# MotorController.net
KiCad netlist of a schematic drawn in Altium Designer
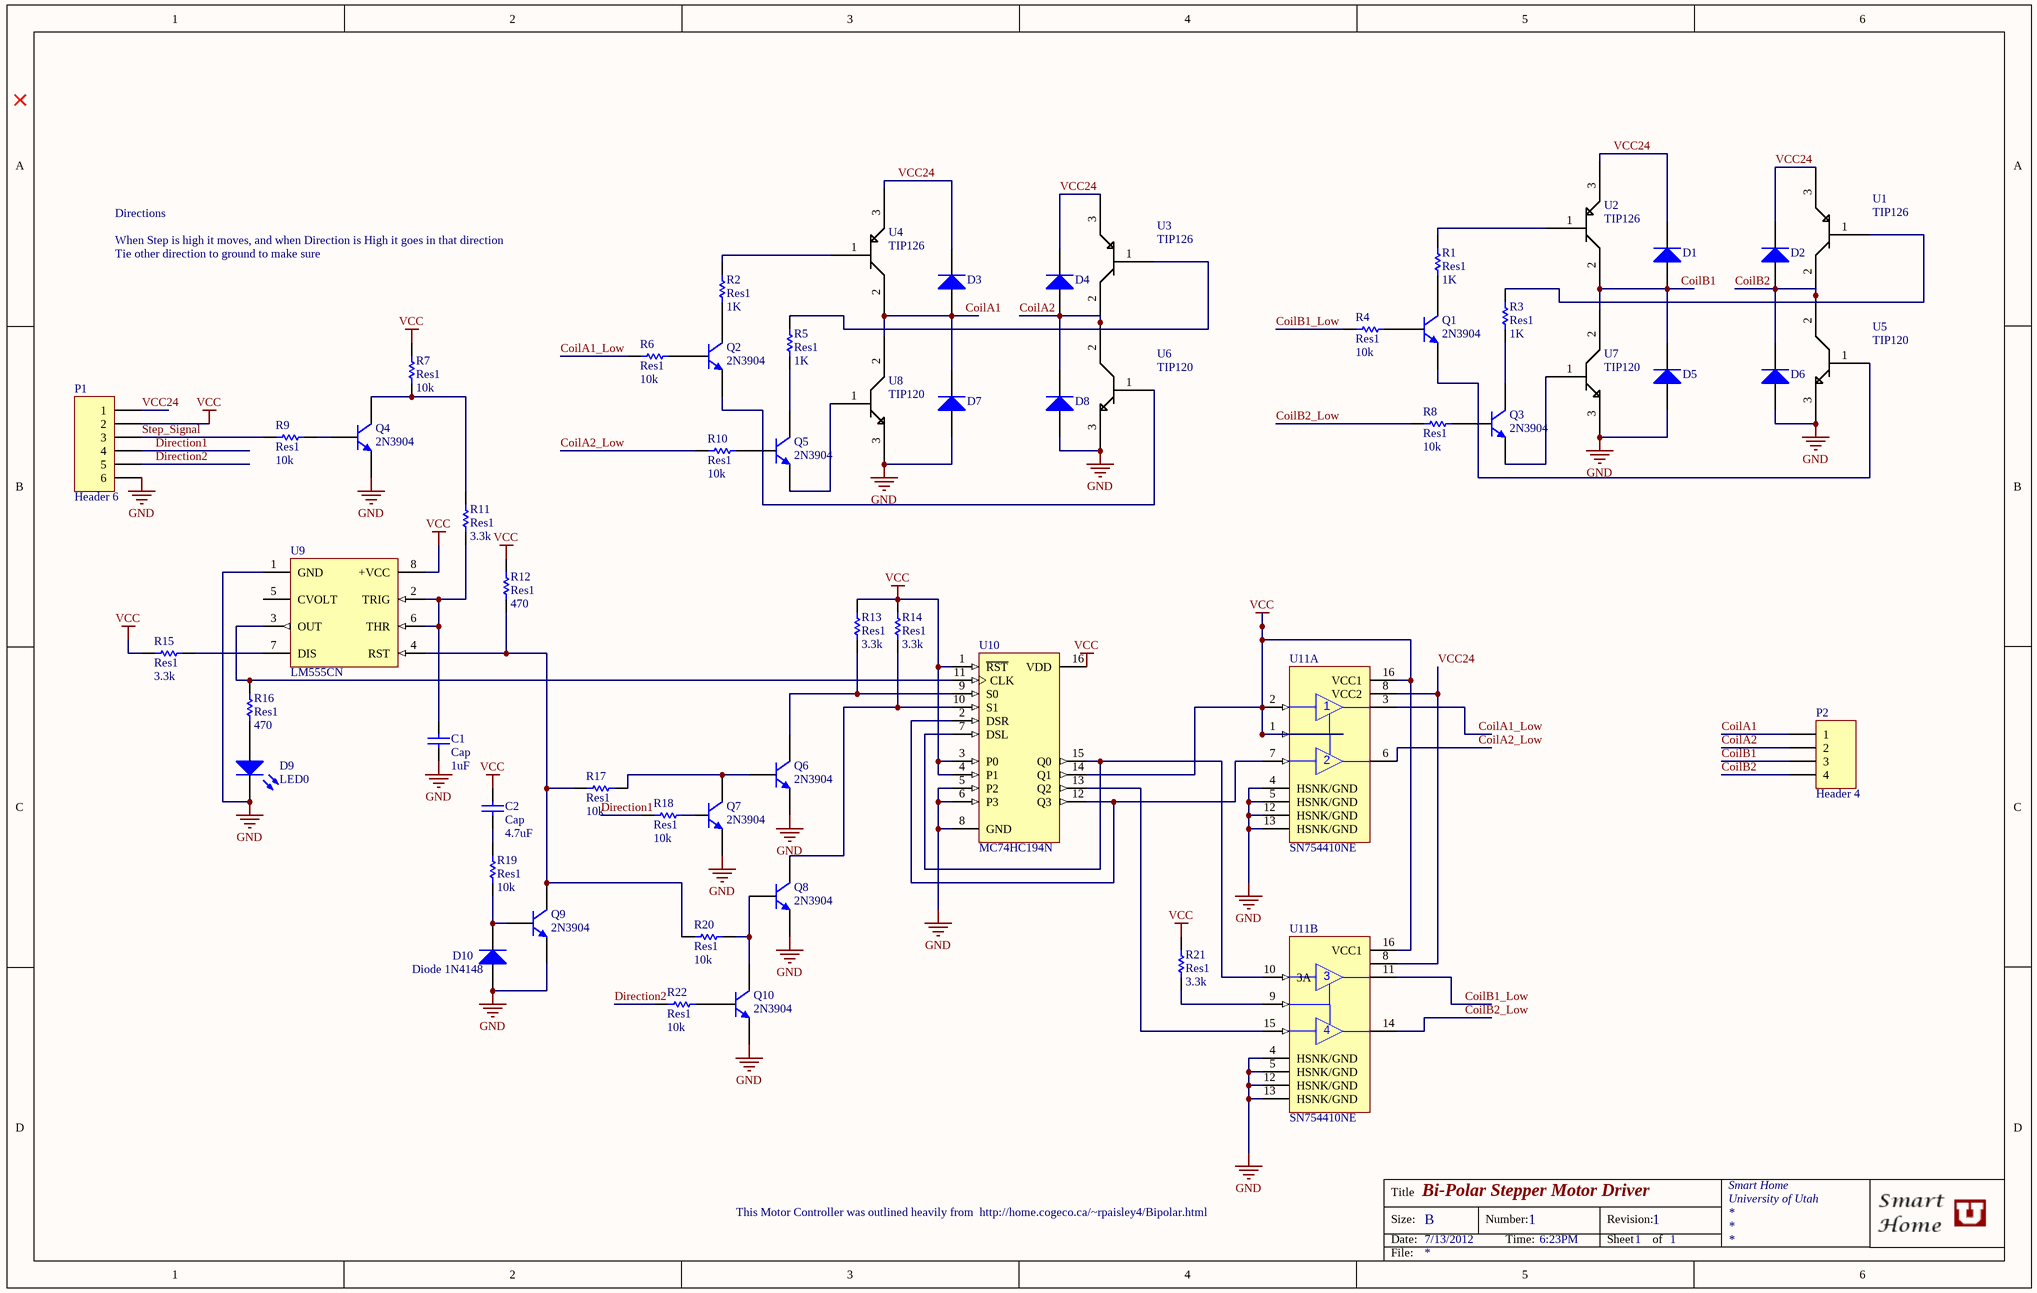
[diagram p0: MotorController.SchDoc]

(export (version "E")
  (design (tool "Eeschema 10.0.6"))
  (components
    (comp (ref "C1")
      (value "Cap")
      (footprint "RAD-0.3")
      (description "Capacitor")
      (fields (field (name "ALTIUM_VALUE") "1uF") (field (name "PUBLISHER") "Altium Limited"))
      (libsource (lib "Miscellaneous Devices") (part "Cap"))
    )
    (comp (ref "C2")
      (value "Cap")
      (footprint "RAD-0.3")
      (description "Capacitor")
      (fields (field (name "ALTIUM_VALUE") "4.7uF") (field (name "PUBLISHER") "Altium Limited"))
      (libsource (lib "Miscellaneous Devices") (part "Cap"))
    )
    (comp (ref "D1")
      (value "Diode 1N5408")
      (footprint "DO-201AD")
      (description "3 Amp Medium Power Silicon Rectifier Diode")
      (fields (field (name "PUBLISHER") "Altium Limited"))
      (libsource (lib "Miscellaneous Devices") (part "Diode 1N5408"))
    )
    (comp (ref "D2")
      (value "Diode 1N5408")
      (footprint "DO-201AD")
      (description "3 Amp Medium Power Silicon Rectifier Diode")
      (fields (field (name "PUBLISHER") "Altium Limited"))
      (libsource (lib "Miscellaneous Devices") (part "Diode 1N5408"))
    )
    (comp (ref "D3")
      (value "Diode 1N5408")
      (footprint "DO-201AD")
      (description "3 Amp Medium Power Silicon Rectifier Diode")
      (fields (field (name "PUBLISHER") "Altium Limited"))
      (libsource (lib "Miscellaneous Devices") (part "Diode 1N5408"))
    )
    (comp (ref "D4")
      (value "Diode 1N5408")
      (footprint "DO-201AD")
      (description "3 Amp Medium Power Silicon Rectifier Diode")
      (fields (field (name "PUBLISHER") "Altium Limited"))
      (libsource (lib "Miscellaneous Devices") (part "Diode 1N5408"))
    )
    (comp (ref "D5")
      (value "Diode 1N5408")
      (footprint "DO-201AD")
      (description "3 Amp Medium Power Silicon Rectifier Diode")
      (fields (field (name "PUBLISHER") "Altium Limited"))
      (libsource (lib "Miscellaneous Devices") (part "Diode 1N5408"))
    )
    (comp (ref "D6")
      (value "Diode 1N5408")
      (footprint "DO-201AD")
      (description "3 Amp Medium Power Silicon Rectifier Diode")
      (fields (field (name "PUBLISHER") "Altium Limited"))
      (libsource (lib "Miscellaneous Devices") (part "Diode 1N5408"))
    )
    (comp (ref "D7")
      (value "Diode 1N5408")
      (footprint "DO-201AD")
      (description "3 Amp Medium Power Silicon Rectifier Diode")
      (fields (field (name "PUBLISHER") "Altium Limited"))
      (libsource (lib "Miscellaneous Devices") (part "Diode 1N5408"))
    )
    (comp (ref "D8")
      (value "Diode 1N5408")
      (footprint "DO-201AD")
      (description "3 Amp Medium Power Silicon Rectifier Diode")
      (fields (field (name "PUBLISHER") "Altium Limited"))
      (libsource (lib "Miscellaneous Devices") (part "Diode 1N5408"))
    )
    (comp (ref "D9")
      (value "LED0")
      (footprint "LED-0")
      (description "Typical INFRARED GaAs LED")
      (fields (field (name "PUBLISHER") "Altium Limited"))
      (libsource (lib "Miscellaneous Devices") (part "LED0"))
    )
    (comp (ref "D10")
      (value "Diode 1N4148")
      (footprint "DO-35")
      (description "High Conductance Fast Diode")
      (fields (field (name "PUBLISHER") "Altium Limited"))
      (libsource (lib "Miscellaneous Devices") (part "Diode 1N4148"))
    )
    (comp (ref "P1")
      (value "Header 6")
      (footprint "HDR1X6")
      (description "Header, 6-Pin")
      (fields (field (name "PUBLISHER") "Altium Limited"))
      (libsource (lib "Miscellaneous Connectors") (part "Header 6"))
    )
    (comp (ref "P2")
      (value "Header 4")
      (footprint "HDR1X4")
      (description "Header, 4-Pin")
      (fields (field (name "PUBLISHER") "Altium Limited"))
      (libsource (lib "Miscellaneous Connectors") (part "Header 4"))
    )
    (comp (ref "Q1")
      (value "2N3904")
      (footprint "2N3904")
      (description "NPN General Purpose Amplifier")
      (fields (field (name "PUBLISHER") "Altium Limited"))
      (libsource (lib "Miscellaneous Devices") (part "2N3904"))
    )
    (comp (ref "Q2")
      (value "2N3904")
      (footprint "2N3904")
      (description "NPN General Purpose Amplifier")
      (fields (field (name "PUBLISHER") "Altium Limited"))
      (libsource (lib "Miscellaneous Devices") (part "2N3904"))
    )
    (comp (ref "Q3")
      (value "2N3904")
      (footprint "2N3904")
      (description "NPN General Purpose Amplifier")
      (fields (field (name "PUBLISHER") "Altium Limited"))
      (libsource (lib "Miscellaneous Devices") (part "2N3904"))
    )
    (comp (ref "Q4")
      (value "2N3904")
      (footprint "2N3904")
      (description "NPN General Purpose Amplifier")
      (fields (field (name "PUBLISHER") "Altium Limited"))
      (libsource (lib "Miscellaneous Devices") (part "2N3904"))
    )
    (comp (ref "Q5")
      (value "2N3904")
      (footprint "2N3904")
      (description "NPN General Purpose Amplifier")
      (fields (field (name "PUBLISHER") "Altium Limited"))
      (libsource (lib "Miscellaneous Devices") (part "2N3904"))
    )
    (comp (ref "Q6")
      (value "2N3904")
      (footprint "2N3904")
      (description "NPN General Purpose Amplifier")
      (fields (field (name "PUBLISHER") "Altium Limited"))
      (libsource (lib "Miscellaneous Devices") (part "2N3904"))
    )
    (comp (ref "Q7")
      (value "2N3904")
      (footprint "2N3904")
      (description "NPN General Purpose Amplifier")
      (fields (field (name "PUBLISHER") "Altium Limited"))
      (libsource (lib "Miscellaneous Devices") (part "2N3904"))
    )
    (comp (ref "Q8")
      (value "2N3904")
      (footprint "2N3904")
      (description "NPN General Purpose Amplifier")
      (fields (field (name "PUBLISHER") "Altium Limited"))
      (libsource (lib "Miscellaneous Devices") (part "2N3904"))
    )
    (comp (ref "Q9")
      (value "2N3904")
      (footprint "2N3904")
      (description "NPN General Purpose Amplifier")
      (fields (field (name "PUBLISHER") "Altium Limited"))
      (libsource (lib "Miscellaneous Devices") (part "2N3904"))
    )
    (comp (ref "Q10")
      (value "2N3904")
      (footprint "2N3904")
      (description "NPN General Purpose Amplifier")
      (fields (field (name "PUBLISHER") "Altium Limited"))
      (libsource (lib "Miscellaneous Devices") (part "2N3904"))
    )
    (comp (ref "R1")
      (value "Res1")
      (footprint "AXIAL-0.3")
      (description "Resistor")
      (fields (field (name "ALTIUM_VALUE") "1K") (field (name "PUBLISHER") "Altium Limited"))
      (libsource (lib "Miscellaneous Devices") (part "Res1"))
    )
    (comp (ref "R2")
      (value "Res1")
      (footprint "AXIAL-0.3")
      (description "Resistor")
      (fields (field (name "ALTIUM_VALUE") "1K") (field (name "PUBLISHER") "Altium Limited"))
      (libsource (lib "Miscellaneous Devices") (part "Res1"))
    )
    (comp (ref "R3")
      (value "Res1")
      (footprint "AXIAL-0.3")
      (description "Resistor")
      (fields (field (name "ALTIUM_VALUE") "1K") (field (name "PUBLISHER") "Altium Limited"))
      (libsource (lib "Miscellaneous Devices") (part "Res1"))
    )
    (comp (ref "R4")
      (value "Res1")
      (footprint "AXIAL-0.3")
      (description "Resistor")
      (fields (field (name "ALTIUM_VALUE") "10k") (field (name "PUBLISHER") "Altium Limited"))
      (libsource (lib "Miscellaneous Devices") (part "Res1"))
    )
    (comp (ref "R5")
      (value "Res1")
      (footprint "AXIAL-0.3")
      (description "Resistor")
      (fields (field (name "ALTIUM_VALUE") "1K") (field (name "PUBLISHER") "Altium Limited"))
      (libsource (lib "Miscellaneous Devices") (part "Res1"))
    )
    (comp (ref "R6")
      (value "Res1")
      (footprint "AXIAL-0.3")
      (description "Resistor")
      (fields (field (name "ALTIUM_VALUE") "10k") (field (name "PUBLISHER") "Altium Limited"))
      (libsource (lib "Miscellaneous Devices") (part "Res1"))
    )
    (comp (ref "R7")
      (value "Res1")
      (footprint "AXIAL-0.3")
      (description "Resistor")
      (fields (field (name "ALTIUM_VALUE") "10k") (field (name "PUBLISHER") "Altium Limited"))
      (libsource (lib "Miscellaneous Devices") (part "Res1"))
    )
    (comp (ref "R8")
      (value "Res1")
      (footprint "AXIAL-0.3")
      (description "Resistor")
      (fields (field (name "ALTIUM_VALUE") "10k") (field (name "PUBLISHER") "Altium Limited"))
      (libsource (lib "Miscellaneous Devices") (part "Res1"))
    )
    (comp (ref "R9")
      (value "Res1")
      (footprint "AXIAL-0.3")
      (description "Resistor")
      (fields (field (name "ALTIUM_VALUE") "10k") (field (name "PUBLISHER") "Altium Limited"))
      (libsource (lib "Miscellaneous Devices") (part "Res1"))
    )
    (comp (ref "R10")
      (value "Res1")
      (footprint "AXIAL-0.3")
      (description "Resistor")
      (fields (field (name "ALTIUM_VALUE") "10k") (field (name "PUBLISHER") "Altium Limited"))
      (libsource (lib "Miscellaneous Devices") (part "Res1"))
    )
    (comp (ref "R11")
      (value "Res1")
      (footprint "AXIAL-0.3")
      (description "Resistor")
      (fields (field (name "ALTIUM_VALUE") "3.3k") (field (name "PUBLISHER") "Altium Limited"))
      (libsource (lib "Miscellaneous Devices") (part "Res1"))
    )
    (comp (ref "R12")
      (value "Res1")
      (footprint "AXIAL-0.3")
      (description "Resistor")
      (fields (field (name "ALTIUM_VALUE") "470") (field (name "PUBLISHER") "Altium Limited"))
      (libsource (lib "Miscellaneous Devices") (part "Res1"))
    )
    (comp (ref "R13")
      (value "Res1")
      (footprint "AXIAL-0.3")
      (description "Resistor")
      (fields (field (name "ALTIUM_VALUE") "3.3k") (field (name "PUBLISHER") "Altium Limited"))
      (libsource (lib "Miscellaneous Devices") (part "Res1"))
    )
    (comp (ref "R14")
      (value "Res1")
      (footprint "AXIAL-0.3")
      (description "Resistor")
      (fields (field (name "ALTIUM_VALUE") "3.3k") (field (name "PUBLISHER") "Altium Limited"))
      (libsource (lib "Miscellaneous Devices") (part "Res1"))
    )
    (comp (ref "R15")
      (value "Res1")
      (footprint "AXIAL-0.3")
      (description "Resistor")
      (fields (field (name "ALTIUM_VALUE") "3.3k") (field (name "PUBLISHER") "Altium Limited"))
      (libsource (lib "Miscellaneous Devices") (part "Res1"))
    )
    (comp (ref "R16")
      (value "Res1")
      (footprint "AXIAL-0.3")
      (description "Resistor")
      (fields (field (name "ALTIUM_VALUE") "470") (field (name "PUBLISHER") "Altium Limited"))
      (libsource (lib "Miscellaneous Devices") (part "Res1"))
    )
    (comp (ref "R17")
      (value "Res1")
      (footprint "AXIAL-0.3")
      (description "Resistor")
      (fields (field (name "ALTIUM_VALUE") "10k") (field (name "PUBLISHER") "Altium Limited"))
      (libsource (lib "Miscellaneous Devices") (part "Res1"))
    )
    (comp (ref "R18")
      (value "Res1")
      (footprint "AXIAL-0.3")
      (description "Resistor")
      (fields (field (name "ALTIUM_VALUE") "10k") (field (name "PUBLISHER") "Altium Limited"))
      (libsource (lib "Miscellaneous Devices") (part "Res1"))
    )
    (comp (ref "R19")
      (value "Res1")
      (footprint "AXIAL-0.3")
      (description "Resistor")
      (fields (field (name "ALTIUM_VALUE") "10k") (field (name "PUBLISHER") "Altium Limited"))
      (libsource (lib "Miscellaneous Devices") (part "Res1"))
    )
    (comp (ref "R20")
      (value "Res1")
      (footprint "AXIAL-0.3")
      (description "Resistor")
      (fields (field (name "ALTIUM_VALUE") "10k") (field (name "PUBLISHER") "Altium Limited"))
      (libsource (lib "Miscellaneous Devices") (part "Res1"))
    )
    (comp (ref "R21")
      (value "Res1")
      (footprint "AXIAL-0.3")
      (description "Resistor")
      (fields (field (name "ALTIUM_VALUE") "3.3k") (field (name "PUBLISHER") "Altium Limited"))
      (libsource (lib "Miscellaneous Devices") (part "Res1"))
    )
    (comp (ref "R22")
      (value "Res1")
      (footprint "AXIAL-0.3")
      (description "Resistor")
      (fields (field (name "ALTIUM_VALUE") "10k") (field (name "PUBLISHER") "Altium Limited"))
      (libsource (lib "Miscellaneous Devices") (part "Res1"))
    )
    (comp (ref "U1")
      (value "TIP126")
      (footprint "TO-220")
      (description "TIP126 -PNP")
      (libsource (lib "SeniorProjectLibrary") (part "TIP126"))
    )
    (comp (ref "U2")
      (value "TIP126")
      (footprint "TO-220")
      (description "TIP126 -PNP")
      (libsource (lib "SeniorProjectLibrary") (part "TIP126"))
    )
    (comp (ref "U3")
      (value "TIP126")
      (footprint "TO-220")
      (description "TIP126 -PNP")
      (libsource (lib "SeniorProjectLibrary") (part "TIP126"))
    )
    (comp (ref "U4")
      (value "TIP126")
      (footprint "TO-220")
      (description "TIP126 -PNP")
      (libsource (lib "SeniorProjectLibrary") (part "TIP126"))
    )
    (comp (ref "U5")
      (value "TIP120")
      (footprint "TO-220")
      (description "NPN 60V -5A TO-220")
      (libsource (lib "SeniorProjectLibrary") (part "TIP120"))
    )
    (comp (ref "U6")
      (value "TIP120")
      (footprint "TO-220")
      (description "NPN 60V -5A TO-220")
      (libsource (lib "SeniorProjectLibrary") (part "TIP120"))
    )
    (comp (ref "U7")
      (value "TIP120")
      (footprint "TO-220")
      (description "NPN 60V -5A TO-220")
      (libsource (lib "SeniorProjectLibrary") (part "TIP120"))
    )
    (comp (ref "U8")
      (value "TIP120")
      (footprint "TO-220")
      (description "NPN 60V -5A TO-220")
      (libsource (lib "SeniorProjectLibrary") (part "TIP120"))
    )
    (comp (ref "U9")
      (value "LM555CN")
      (footprint "N08E")
      (description "Timer")
      (fields
        (field (name "MANUFACTURER") "National Semiconductor")
        (field (name "DIGIKEYPARTNUMBER") "LM555CNNS-ND")
        (field (name "PUBLISHER") "Altium Limited")
      )
      (libsource (lib "NSC Analog") (part "LM555CN"))
    )
    (comp (ref "U10")
      (value "MC74HC194N")
      (footprint "648-06")
      (description "4-Bit Bidirectional Universal Shift Register")
      (fields (field (name "PUBLISHER") "Altium Limited"))
      (libsource (lib "Motorola Logic Register") (part "MC74HC194N"))
    )
    (comp (ref "U11")
      (value "SN754410NE")
      (footprint "NE016")
      (description "Quadruple Half-H Driver")
      (fields (field (name "PUBLISHER") "Altium Limited"))
      (libsource (lib "TI Interface Peripheral Driver") (part "SN754410NE"))
    )
  )
  (nets
    (net (code "1") (name "/CoilA1") (class "Default")
      (node (ref "D3") (pin "1") (pinfunction "A_1") (pintype "passive"))
      (node (ref "D7") (pin "2") (pinfunction "K_2") (pintype "passive"))
      (node (ref "P2") (pin "1") (pinfunction "1_1") (pintype "passive"))
      (node (ref "U4") (pin "2") (pinfunction "2_2") (pintype "passive"))
      (node (ref "U8") (pin "2") (pinfunction "2_2") (pintype "passive"))
    )
    (net (code "2") (name "/CoilA1_Low") (class "Default")
      (node (ref "R6") (pin "1") (pinfunction "1_1") (pintype "passive"))
      (node (ref "U11") (pin "3") (pinfunction "1Y_3") (pintype "tri_state"))
    )
    (net (code "3") (name "/CoilA2") (class "Default")
      (node (ref "D4") (pin "1") (pinfunction "A_1") (pintype "passive"))
      (node (ref "D8") (pin "2") (pinfunction "K_2") (pintype "passive"))
      (node (ref "P2") (pin "2") (pinfunction "2_2") (pintype "passive"))
      (node (ref "U3") (pin "2") (pinfunction "2_2") (pintype "passive"))
      (node (ref "U6") (pin "2") (pinfunction "2_2") (pintype "passive"))
    )
    (net (code "4") (name "/CoilA2_Low") (class "Default")
      (node (ref "R10") (pin "1") (pinfunction "1_1") (pintype "passive"))
      (node (ref "U11") (pin "6") (pinfunction "2Y_6") (pintype "tri_state"))
    )
    (net (code "5") (name "/CoilB1") (class "Default")
      (node (ref "D1") (pin "1") (pinfunction "A_1") (pintype "passive"))
      (node (ref "D5") (pin "2") (pinfunction "K_2") (pintype "passive"))
      (node (ref "P2") (pin "3") (pinfunction "3_3") (pintype "passive"))
      (node (ref "U2") (pin "2") (pinfunction "2_2") (pintype "passive"))
      (node (ref "U7") (pin "2") (pinfunction "2_2") (pintype "passive"))
    )
    (net (code "6") (name "/CoilB1_Low") (class "Default")
      (node (ref "R4") (pin "1") (pinfunction "1_1") (pintype "passive"))
      (node (ref "U11") (pin "11") (pinfunction "3Y_11") (pintype "tri_state"))
    )
    (net (code "7") (name "/CoilB2") (class "Default")
      (node (ref "D2") (pin "1") (pinfunction "A_1") (pintype "passive"))
      (node (ref "D6") (pin "2") (pinfunction "K_2") (pintype "passive"))
      (node (ref "P2") (pin "4") (pinfunction "4_4") (pintype "passive"))
      (node (ref "U1") (pin "2") (pinfunction "2_2") (pintype "passive"))
      (node (ref "U5") (pin "2") (pinfunction "2_2") (pintype "passive"))
    )
    (net (code "8") (name "/CoilB2_Low") (class "Default")
      (node (ref "R8") (pin "1") (pinfunction "1_1") (pintype "passive"))
      (node (ref "U11") (pin "14") (pinfunction "4Y_14") (pintype "tri_state"))
    )
    (net (code "9") (name "/Direction1") (class "Default")
      (node (ref "P1") (pin "4") (pinfunction "4_4") (pintype "passive"))
      (node (ref "R18") (pin "2") (pinfunction "2_2") (pintype "passive"))
    )
    (net (code "10") (name "/Direction2") (class "Default")
      (node (ref "P1") (pin "5") (pinfunction "5_5") (pintype "passive"))
      (node (ref "R22") (pin "2") (pinfunction "2_2") (pintype "passive"))
    )
    (net (code "11") (name "/Step_Signal") (class "Default")
      (node (ref "P1") (pin "3") (pinfunction "3_3") (pintype "passive"))
      (node (ref "R9") (pin "2") (pinfunction "2_2") (pintype "passive"))
    )
    (net (code "12") (name "/VCC24") (class "Default")
      (node (ref "D1") (pin "2") (pinfunction "K_2") (pintype "passive"))
      (node (ref "D2") (pin "2") (pinfunction "K_2") (pintype "passive"))
      (node (ref "D3") (pin "2") (pinfunction "K_2") (pintype "passive"))
      (node (ref "D4") (pin "2") (pinfunction "K_2") (pintype "passive"))
      (node (ref "P1") (pin "1") (pinfunction "1_1") (pintype "passive"))
      (node (ref "U1") (pin "3") (pinfunction "3_3") (pintype "passive"))
      (node (ref "U11") (pin "8") (pinfunction "VCC2_8") (pintype "power_in"))
      (node (ref "U2") (pin "3") (pinfunction "3_3") (pintype "passive"))
      (node (ref "U3") (pin "3") (pinfunction "3_3") (pintype "passive"))
      (node (ref "U4") (pin "3") (pinfunction "3_3") (pintype "passive"))
    )
    (net (code "13") (name "GND") (class "Default")
      (node (ref "C1") (pin "2") (pinfunction "2_2") (pintype "passive"))
      (node (ref "D10") (pin "1") (pinfunction "A_1") (pintype "passive"))
      (node (ref "D5") (pin "1") (pinfunction "A_1") (pintype "passive"))
      (node (ref "D6") (pin "1") (pinfunction "A_1") (pintype "passive"))
      (node (ref "D7") (pin "1") (pinfunction "A_1") (pintype "passive"))
      (node (ref "D8") (pin "1") (pinfunction "A_1") (pintype "passive"))
      (node (ref "D9") (pin "2") (pinfunction "K_2") (pintype "passive"))
      (node (ref "P1") (pin "6") (pinfunction "6_6") (pintype "passive"))
      (node (ref "Q10") (pin "1") (pinfunction "E_1") (pintype "passive"))
      (node (ref "Q4") (pin "1") (pinfunction "E_1") (pintype "passive"))
      (node (ref "Q6") (pin "1") (pinfunction "E_1") (pintype "passive"))
      (node (ref "Q7") (pin "1") (pinfunction "E_1") (pintype "passive"))
      (node (ref "Q8") (pin "1") (pinfunction "E_1") (pintype "passive"))
      (node (ref "Q9") (pin "1") (pinfunction "E_1") (pintype "passive"))
      (node (ref "U10") (pin "5") (pinfunction "P2_5") (pintype "input"))
      (node (ref "U10") (pin "6") (pinfunction "P3_6") (pintype "input"))
      (node (ref "U10") (pin "8") (pinfunction "GND_8") (pintype "power_in"))
      (node (ref "U11") (pin "12") (pinfunction "HSNK/GND_12") (pintype "power_in"))
      (node (ref "U11") (pin "13") (pinfunction "HSNK/GND_13") (pintype "power_in"))
      (node (ref "U11") (pin "4") (pinfunction "HSNK/GND_4") (pintype "power_in"))
      (node (ref "U11") (pin "5") (pinfunction "HSNK/GND_5") (pintype "power_in"))
      (node (ref "U5") (pin "3") (pinfunction "3_3") (pintype "passive"))
      (node (ref "U6") (pin "3") (pinfunction "3_3") (pintype "passive"))
      (node (ref "U7") (pin "3") (pinfunction "3_3") (pintype "passive"))
      (node (ref "U8") (pin "3") (pinfunction "3_3") (pintype "passive"))
      (node (ref "U9") (pin "1") (pinfunction "GND_1") (pintype "power_in"))
    )
    (net (code "14") (name "Net-(C2-Pad2)") (class "Default")
      (node (ref "C2") (pin "2") (pinfunction "2_2") (pintype "passive"))
      (node (ref "R19") (pin "1") (pinfunction "1_1") (pintype "passive"))
    )
    (net (code "15") (name "Net-(D9-A)") (class "Default")
      (node (ref "D9") (pin "1") (pinfunction "A_1") (pintype "passive"))
      (node (ref "R16") (pin "2") (pinfunction "2_2") (pintype "passive"))
    )
    (net (code "16") (name "Net-(D10-K)") (class "Default")
      (node (ref "D10") (pin "2") (pinfunction "K_2") (pintype "passive"))
      (node (ref "Q9") (pin "2") (pinfunction "B_2") (pintype "passive"))
      (node (ref "R19") (pin "2") (pinfunction "2_2") (pintype "passive"))
    )
    (net (code "17") (name "Net-(Q1-B)") (class "Default")
      (node (ref "Q1") (pin "2") (pinfunction "B_2") (pintype "passive"))
      (node (ref "R4") (pin "2") (pinfunction "2_2") (pintype "passive"))
    )
    (net (code "18") (name "Net-(Q1-C)") (class "Default")
      (node (ref "Q1") (pin "3") (pinfunction "C_3") (pintype "passive"))
      (node (ref "R1") (pin "1") (pinfunction "1_1") (pintype "passive"))
    )
    (net (code "19") (name "Net-(Q1-E)") (class "Default")
      (node (ref "Q1") (pin "1") (pinfunction "E_1") (pintype "passive"))
      (node (ref "U5") (pin "1") (pinfunction "1_1") (pintype "passive"))
    )
    (net (code "20") (name "Net-(Q2-B)") (class "Default")
      (node (ref "Q2") (pin "2") (pinfunction "B_2") (pintype "passive"))
      (node (ref "R6") (pin "2") (pinfunction "2_2") (pintype "passive"))
    )
    (net (code "21") (name "Net-(Q2-C)") (class "Default")
      (node (ref "Q2") (pin "3") (pinfunction "C_3") (pintype "passive"))
      (node (ref "R2") (pin "1") (pinfunction "1_1") (pintype "passive"))
    )
    (net (code "22") (name "Net-(Q2-E)") (class "Default")
      (node (ref "Q2") (pin "1") (pinfunction "E_1") (pintype "passive"))
      (node (ref "U6") (pin "1") (pinfunction "1_1") (pintype "passive"))
    )
    (net (code "23") (name "Net-(Q3-B)") (class "Default")
      (node (ref "Q3") (pin "2") (pinfunction "B_2") (pintype "passive"))
      (node (ref "R8") (pin "2") (pinfunction "2_2") (pintype "passive"))
    )
    (net (code "24") (name "Net-(Q3-C)") (class "Default")
      (node (ref "Q3") (pin "3") (pinfunction "C_3") (pintype "passive"))
      (node (ref "R3") (pin "1") (pinfunction "1_1") (pintype "passive"))
    )
    (net (code "25") (name "Net-(Q3-E)") (class "Default")
      (node (ref "Q3") (pin "1") (pinfunction "E_1") (pintype "passive"))
      (node (ref "U7") (pin "1") (pinfunction "1_1") (pintype "passive"))
    )
    (net (code "26") (name "Net-(Q4-B)") (class "Default")
      (node (ref "Q4") (pin "2") (pinfunction "B_2") (pintype "passive"))
      (node (ref "R9") (pin "1") (pinfunction "1_1") (pintype "passive"))
    )
    (net (code "27") (name "Net-(Q4-C)") (class "Default")
      (node (ref "Q4") (pin "3") (pinfunction "C_3") (pintype "passive"))
      (node (ref "R11") (pin "2") (pinfunction "2_2") (pintype "passive"))
      (node (ref "R7") (pin "1") (pinfunction "1_1") (pintype "passive"))
    )
    (net (code "28") (name "Net-(Q5-B)") (class "Default")
      (node (ref "Q5") (pin "2") (pinfunction "B_2") (pintype "passive"))
      (node (ref "R10") (pin "2") (pinfunction "2_2") (pintype "passive"))
    )
    (net (code "29") (name "Net-(Q5-C)") (class "Default")
      (node (ref "Q5") (pin "3") (pinfunction "C_3") (pintype "passive"))
      (node (ref "R5") (pin "1") (pinfunction "1_1") (pintype "passive"))
    )
    (net (code "30") (name "Net-(Q5-E)") (class "Default")
      (node (ref "Q5") (pin "1") (pinfunction "E_1") (pintype "passive"))
      (node (ref "U8") (pin "1") (pinfunction "1_1") (pintype "passive"))
    )
    (net (code "31") (name "Net-(Q6-B)") (class "Default")
      (node (ref "Q6") (pin "2") (pinfunction "B_2") (pintype "passive"))
      (node (ref "Q7") (pin "3") (pinfunction "C_3") (pintype "passive"))
      (node (ref "R17") (pin "2") (pinfunction "2_2") (pintype "passive"))
    )
    (net (code "32") (name "Net-(Q6-C)") (class "Default")
      (node (ref "Q6") (pin "3") (pinfunction "C_3") (pintype "passive"))
      (node (ref "R13") (pin "2") (pinfunction "2_2") (pintype "passive"))
      (node (ref "U10") (pin "9") (pinfunction "S0_9") (pintype "input"))
    )
    (net (code "33") (name "Net-(Q7-B)") (class "Default")
      (node (ref "Q7") (pin "2") (pinfunction "B_2") (pintype "passive"))
      (node (ref "R18") (pin "1") (pinfunction "1_1") (pintype "passive"))
    )
    (net (code "34") (name "Net-(Q8-C)") (class "Default")
      (node (ref "Q8") (pin "3") (pinfunction "C_3") (pintype "passive"))
      (node (ref "R14") (pin "2") (pinfunction "2_2") (pintype "passive"))
      (node (ref "U10") (pin "10") (pinfunction "S1_10") (pintype "input"))
    )
    (net (code "35") (name "Net-(Q9-C)") (class "Default")
      (node (ref "Q9") (pin "3") (pinfunction "C_3") (pintype "passive"))
      (node (ref "R12") (pin "2") (pinfunction "2_2") (pintype "passive"))
      (node (ref "R17") (pin "1") (pinfunction "1_1") (pintype "passive"))
      (node (ref "R20") (pin "1") (pinfunction "1_1") (pintype "passive"))
      (node (ref "U9") (pin "4") (pinfunction "RST_4") (pintype "input"))
    )
    (net (code "36") (name "Net-(Q10-B)") (class "Default")
      (node (ref "Q10") (pin "2") (pinfunction "B_2") (pintype "passive"))
      (node (ref "R22") (pin "1") (pinfunction "1_1") (pintype "passive"))
    )
    (net (code "37") (name "Net-(Q10-C)") (class "Default")
      (node (ref "Q10") (pin "3") (pinfunction "C_3") (pintype "passive"))
      (node (ref "Q8") (pin "2") (pinfunction "B_2") (pintype "passive"))
      (node (ref "R20") (pin "2") (pinfunction "2_2") (pintype "passive"))
    )
    (net (code "38") (name "Net-(R1-Pad2)") (class "Default")
      (node (ref "R1") (pin "2") (pinfunction "2_2") (pintype "passive"))
      (node (ref "U2") (pin "1") (pinfunction "1_1") (pintype "passive"))
    )
    (net (code "39") (name "Net-(R2-Pad2)") (class "Default")
      (node (ref "R2") (pin "2") (pinfunction "2_2") (pintype "passive"))
      (node (ref "U4") (pin "1") (pinfunction "1_1") (pintype "passive"))
    )
    (net (code "40") (name "Net-(R3-Pad2)") (class "Default")
      (node (ref "R3") (pin "2") (pinfunction "2_2") (pintype "passive"))
      (node (ref "U1") (pin "1") (pinfunction "1_1") (pintype "passive"))
    )
    (net (code "41") (name "Net-(R5-Pad2)") (class "Default")
      (node (ref "R5") (pin "2") (pinfunction "2_2") (pintype "passive"))
      (node (ref "U3") (pin "1") (pinfunction "1_1") (pintype "passive"))
    )
    (net (code "42") (name "Net-(U9-DIS)") (class "Default")
      (node (ref "R15") (pin "1") (pinfunction "1_1") (pintype "passive"))
      (node (ref "U9") (pin "7") (pinfunction "DIS_7") (pintype "open_collector"))
    )
    (net (code "43") (name "Net-(U9-THR)") (class "Default")
      (node (ref "C1") (pin "1") (pinfunction "1_1") (pintype "passive"))
      (node (ref "R11") (pin "1") (pinfunction "1_1") (pintype "passive"))
      (node (ref "U9") (pin "2") (pinfunction "TRIG_2") (pintype "input"))
      (node (ref "U9") (pin "6") (pinfunction "THR_6") (pintype "input"))
    )
    (net (code "44") (name "Net-(U10-CLK)") (class "Default")
      (node (ref "R16") (pin "1") (pinfunction "1_1") (pintype "passive"))
      (node (ref "U10") (pin "11") (pinfunction "CLK_11") (pintype "input"))
      (node (ref "U9") (pin "3") (pinfunction "OUT_3") (pintype "output"))
    )
    (net (code "45") (name "Net-(U10-DSL)") (class "Default")
      (node (ref "U10") (pin "15") (pinfunction "Q0_15") (pintype "output"))
      (node (ref "U10") (pin "7") (pinfunction "DSL_7") (pintype "input"))
      (node (ref "U11") (pin "10") (pinfunction "3A_10") (pintype "input"))
    )
    (net (code "46") (name "Net-(U10-DSR)") (class "Default")
      (node (ref "U10") (pin "12") (pinfunction "Q3_12") (pintype "output"))
      (node (ref "U10") (pin "2") (pinfunction "DSR_2") (pintype "input"))
      (node (ref "U11") (pin "7") (pinfunction "2A_7") (pintype "input"))
    )
    (net (code "47") (name "Net-(U10-Q2)") (class "Default")
      (node (ref "U10") (pin "13") (pinfunction "Q2_13") (pintype "output"))
      (node (ref "U11") (pin "15") (pinfunction "4A_15") (pintype "input"))
    )
    (net (code "48") (name "Net-(U11B-3,4EN)") (class "Default")
      (node (ref "R21") (pin "2") (pinfunction "2_2") (pintype "passive"))
      (node (ref "U11") (pin "9") (pinfunction "3,4EN_9") (pintype "input"))
    )
    (net (code "49") (name "VCC") (class "Default")
      (node (ref "C2") (pin "1") (pinfunction "1_1") (pintype "passive"))
      (node (ref "P1") (pin "2") (pinfunction "2_2") (pintype "passive"))
      (node (ref "R12") (pin "1") (pinfunction "1_1") (pintype "passive"))
      (node (ref "R13") (pin "1") (pinfunction "1_1") (pintype "passive"))
      (node (ref "R14") (pin "1") (pinfunction "1_1") (pintype "passive"))
      (node (ref "R15") (pin "2") (pinfunction "2_2") (pintype "passive"))
      (node (ref "R21") (pin "1") (pinfunction "1_1") (pintype "passive"))
      (node (ref "R7") (pin "2") (pinfunction "2_2") (pintype "passive"))
      (node (ref "U10") (pin "1") (pinfunction "~{RST}_1") (pintype "input"))
      (node (ref "U10") (pin "14") (pinfunction "Q1_14") (pintype "output"))
      (node (ref "U10") (pin "16") (pinfunction "VDD_16") (pintype "power_in"))
      (node (ref "U10") (pin "3") (pinfunction "P0_3") (pintype "input"))
      (node (ref "U10") (pin "4") (pinfunction "P1_4") (pintype "input"))
      (node (ref "U11") (pin "1") (pinfunction "1,2EN_1") (pintype "input"))
      (node (ref "U11") (pin "16") (pinfunction "VCC1_16") (pintype "power_in"))
      (node (ref "U11") (pin "2") (pinfunction "1A_2") (pintype "input"))
      (node (ref "U9") (pin "8") (pinfunction "+VCC_8") (pintype "power_in"))
    )
    (net (code "50") (name "unconnected-(U9-CVOLT-Pad5)") (class "Default")
      (node (ref "U9") (pin "5") (pinfunction "CVOLT_5") (pintype "passive"))
    )
  )
)
